# design.net
KiCad netlist of a schematic drawn in EasyEDA Pro
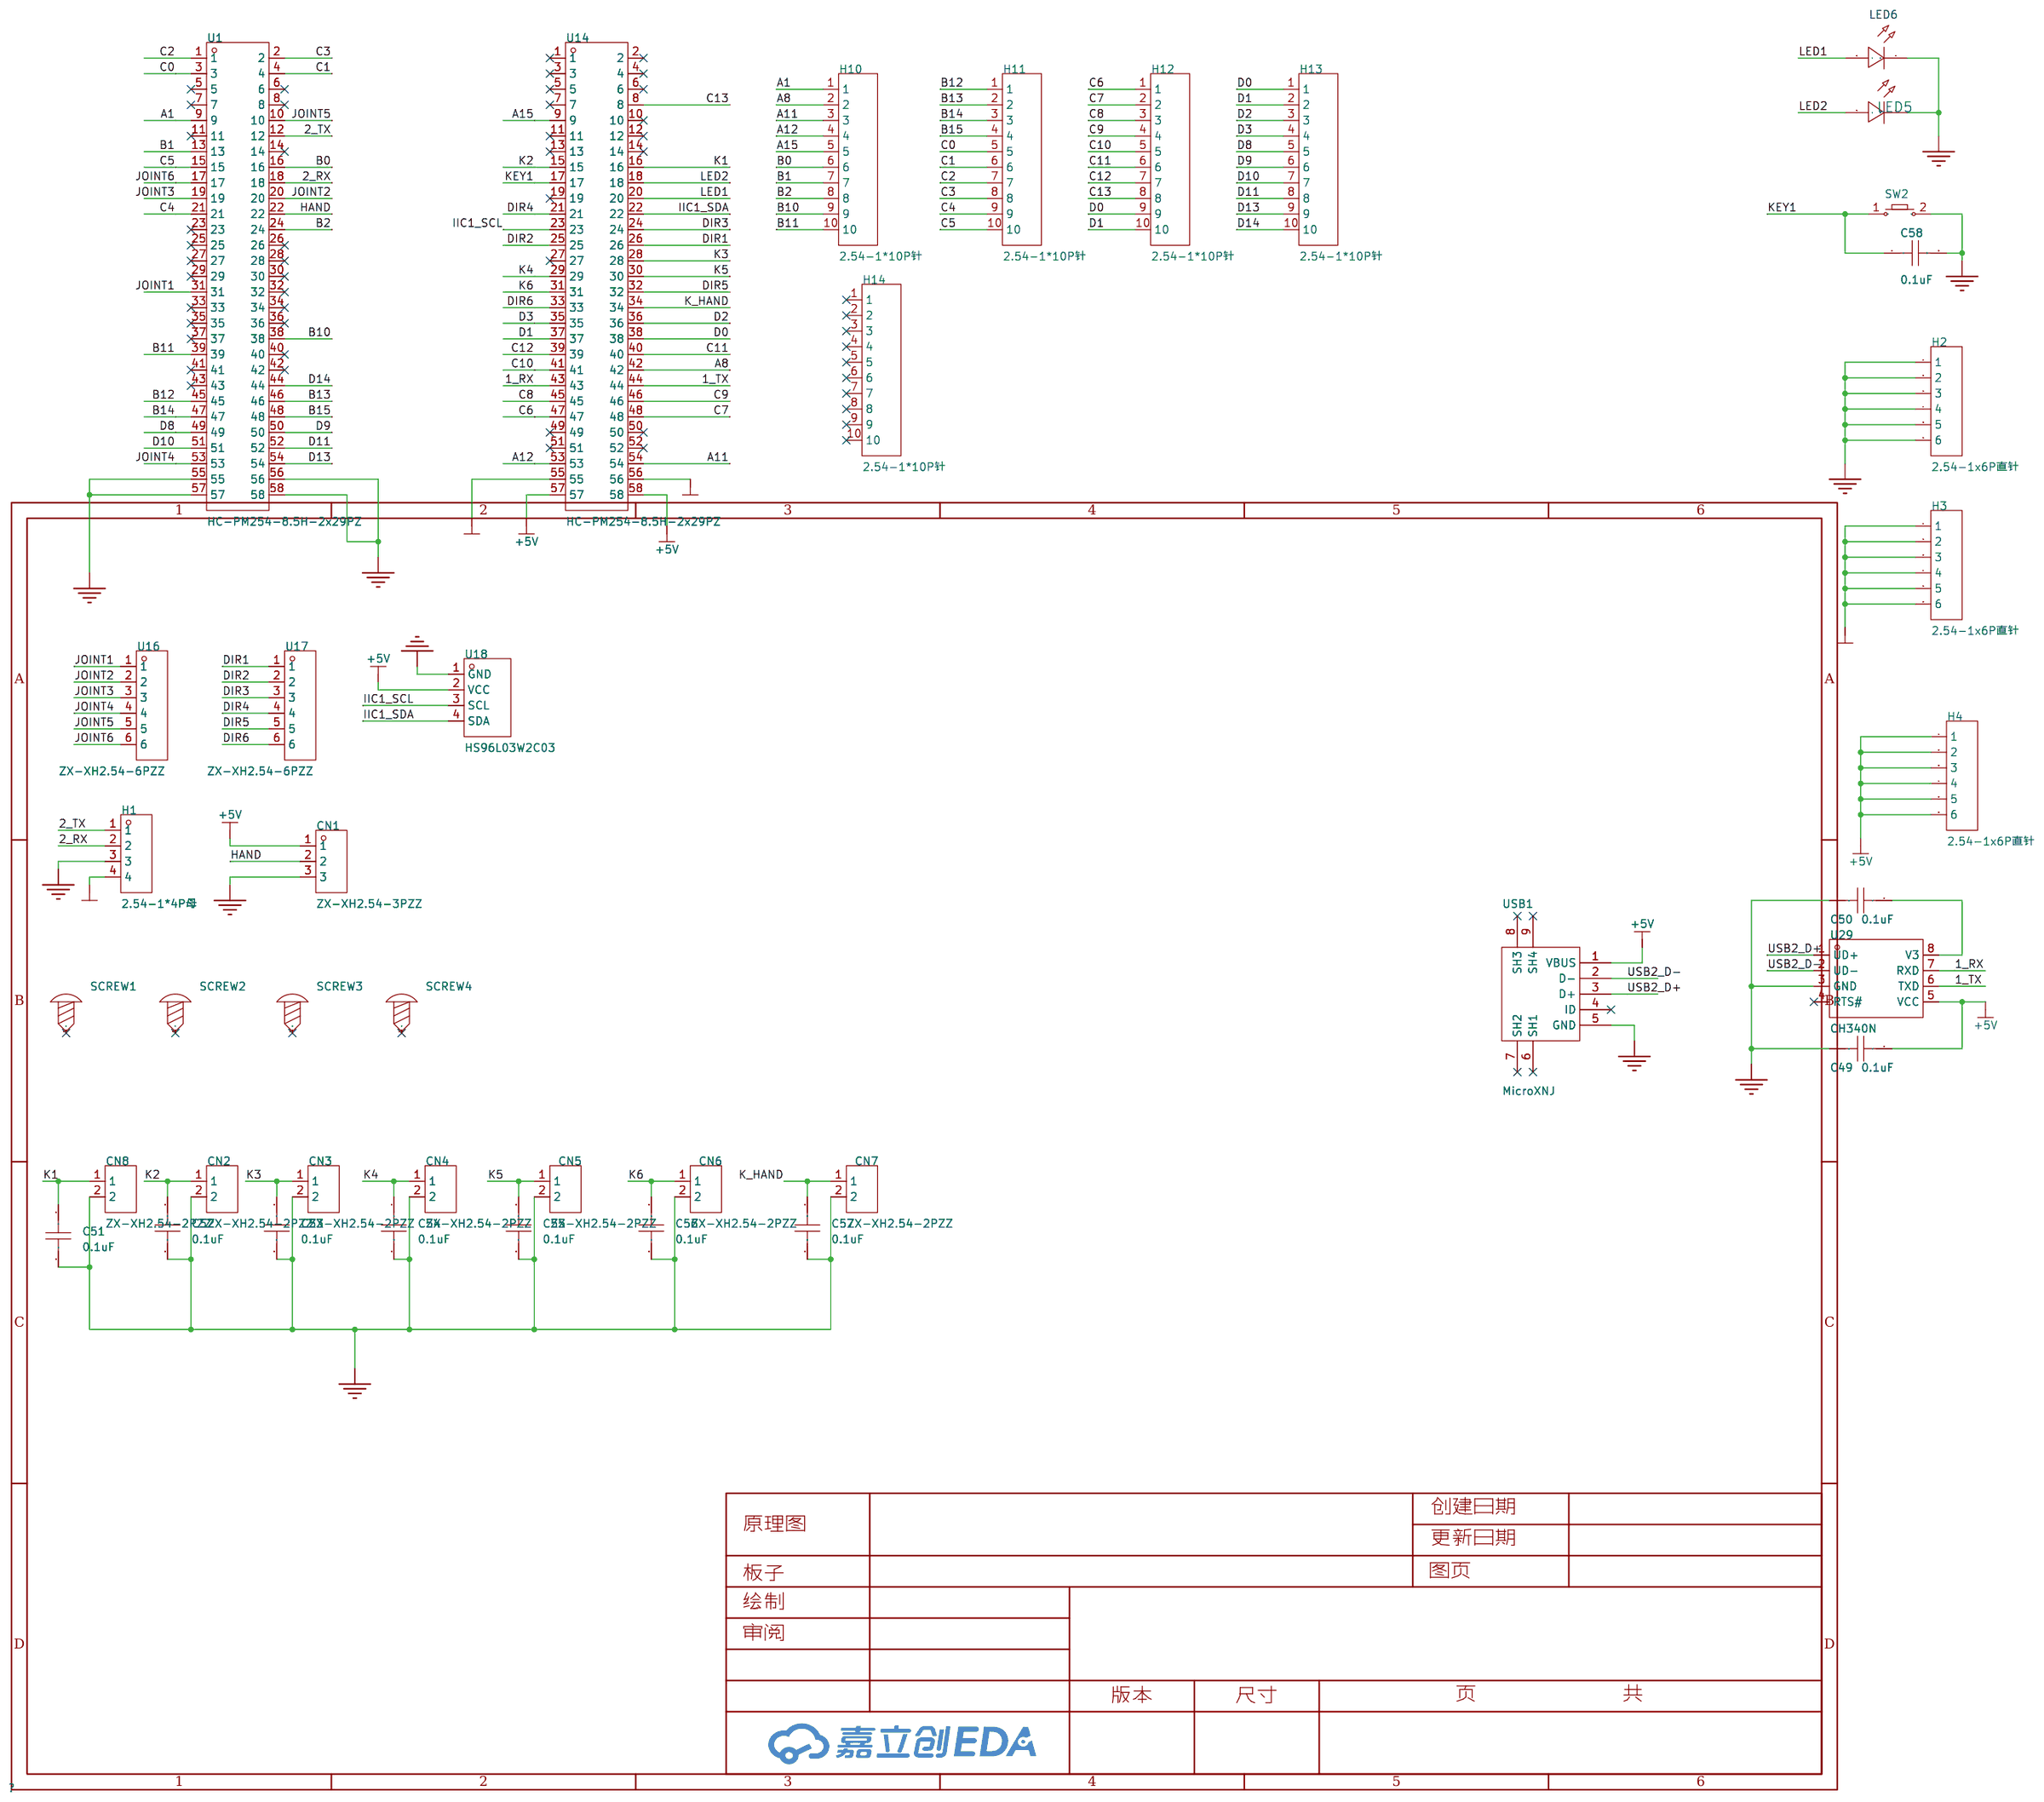
[diagram p0: 控制]
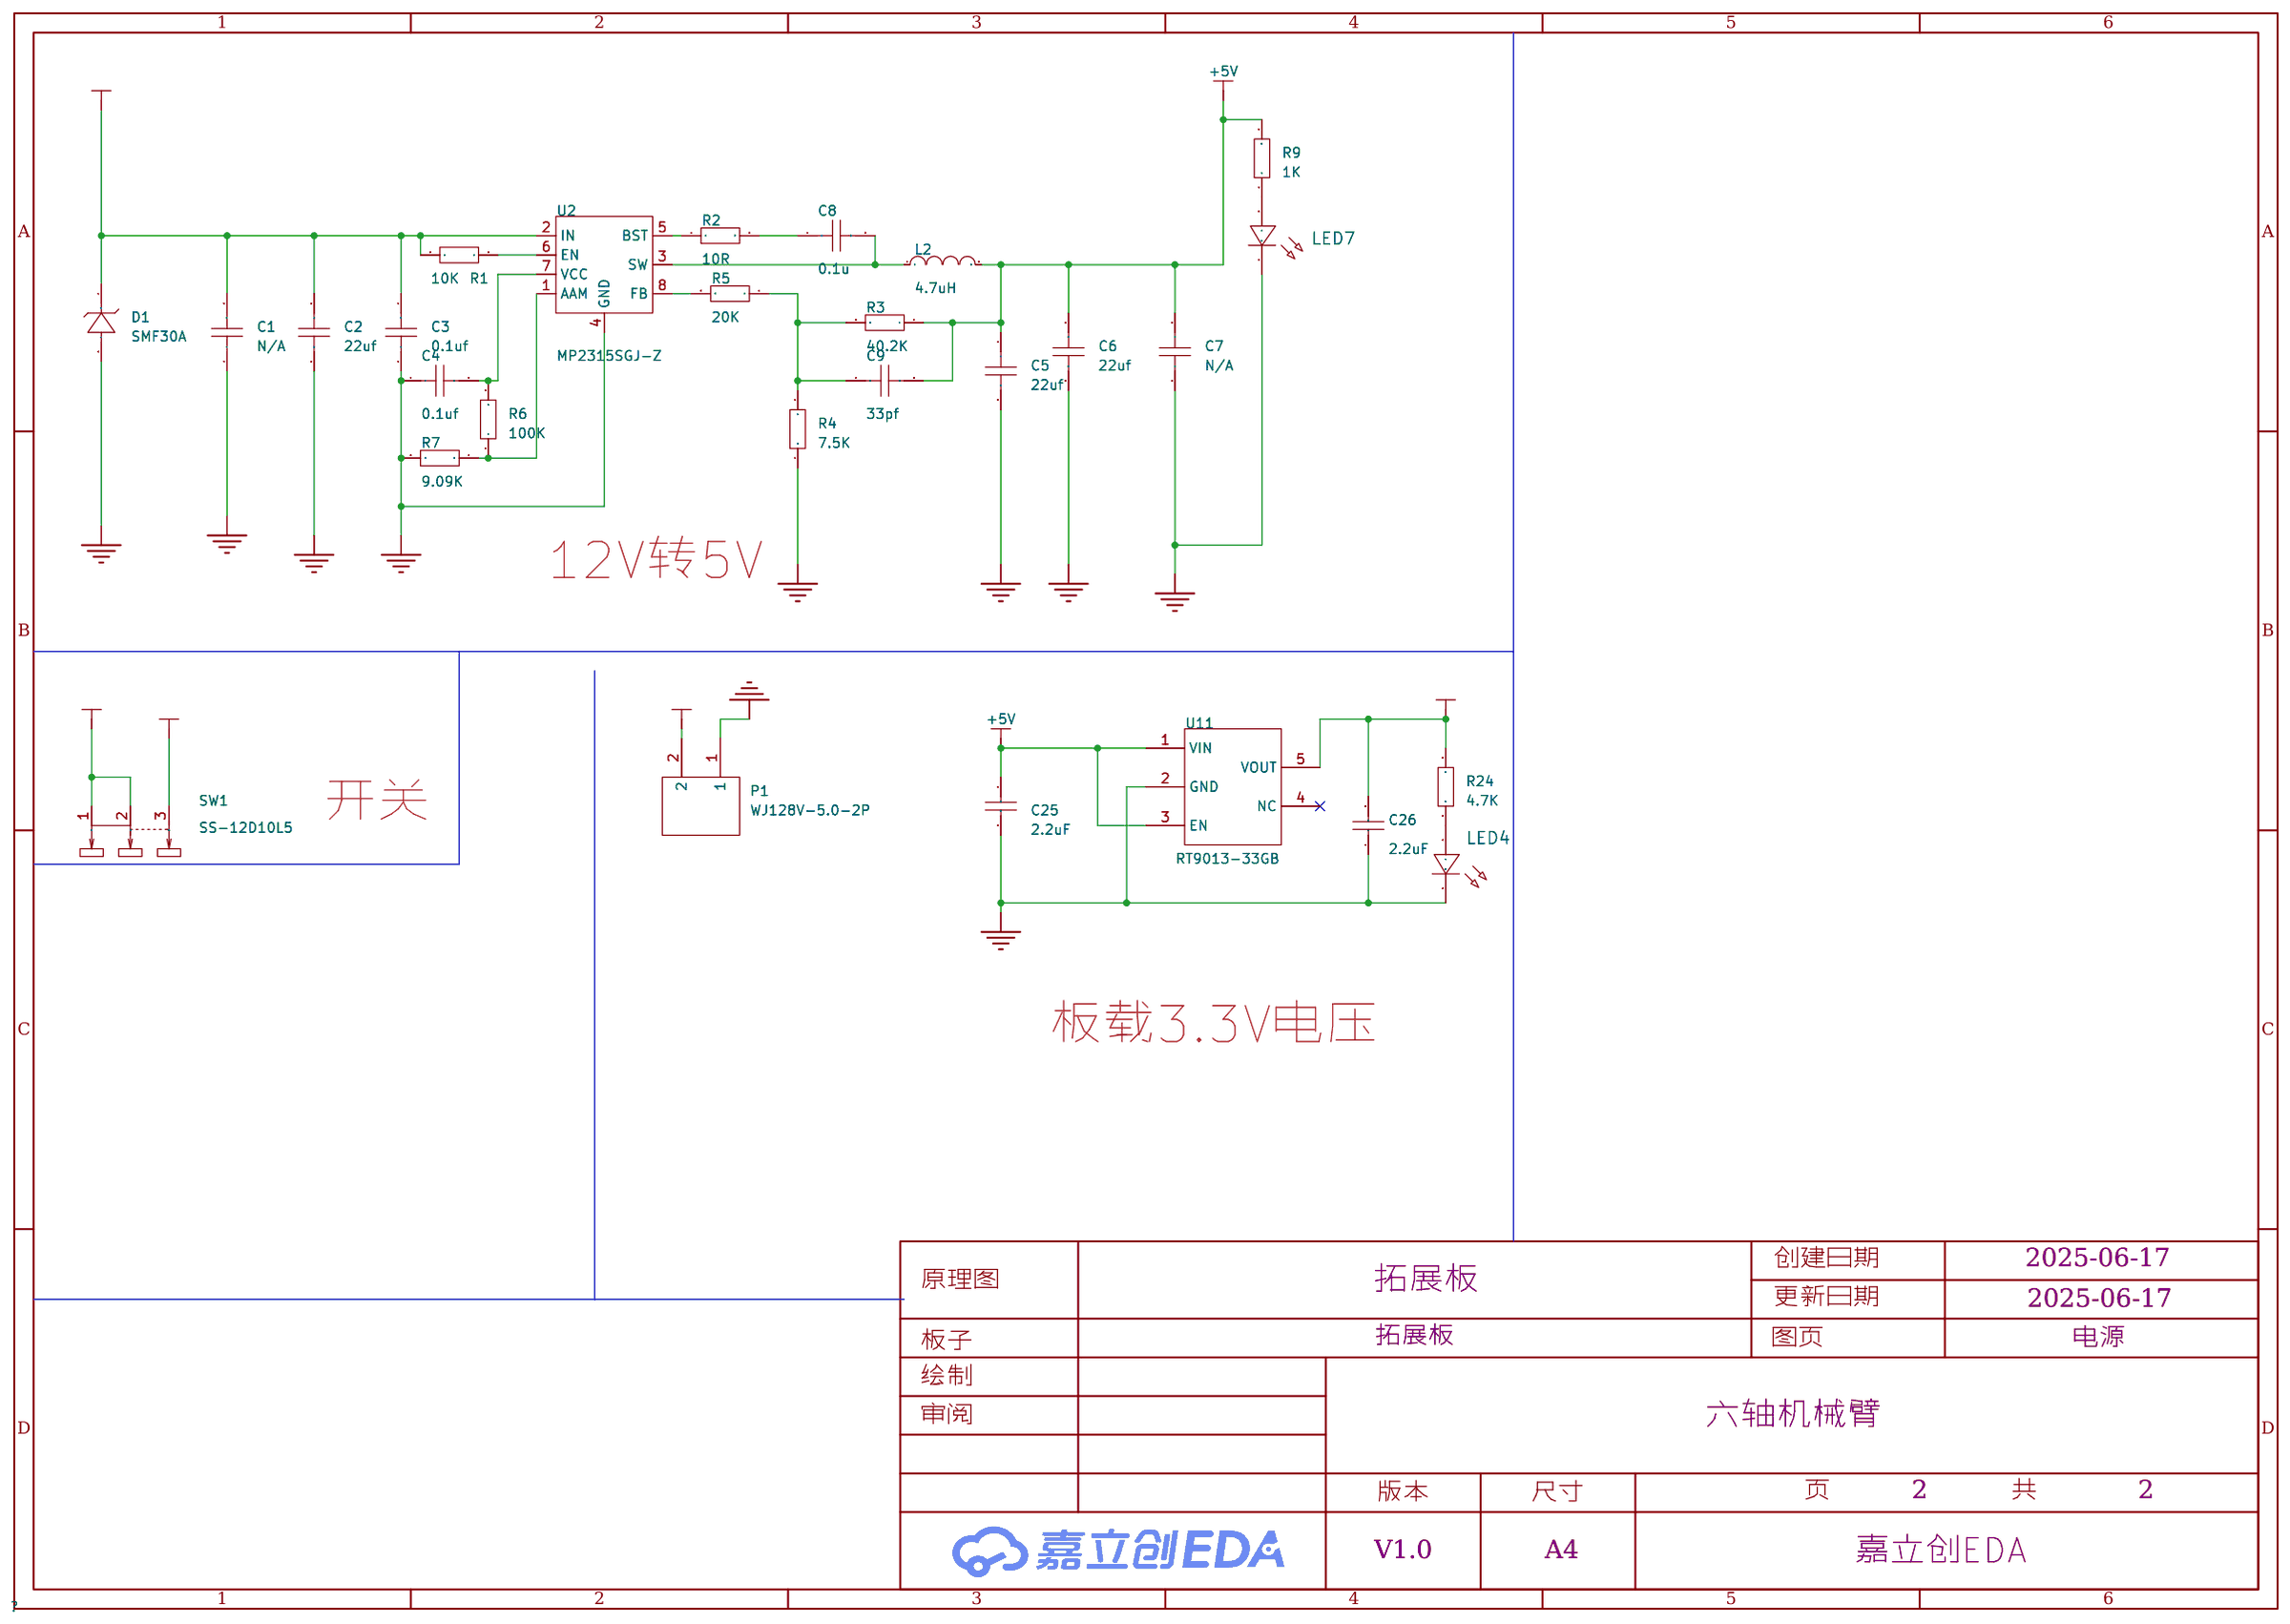
[diagram p1: 电源]

(export (version "E")
  (design (tool "Eeschema 10.0.6"))
  (components
    (comp (ref "C49")
      (value "0.1uF")
      (footprint "easyedapro:C0805")
      (libsource (lib "easyedapro") (part "CapAcitance"))
    )
    (comp (ref "C50")
      (value "0.1uF")
      (footprint "easyedapro:C0805")
      (libsource (lib "easyedapro") (part "CapAcitance"))
    )
    (comp (ref "C51")
      (value "0.1uF")
      (footprint "easyedapro:C0805")
      (libsource (lib "easyedapro") (part "CapAcitance"))
    )
    (comp (ref "C52")
      (value "0.1uF")
      (footprint "easyedapro:C0805")
      (libsource (lib "easyedapro") (part "CapAcitance"))
    )
    (comp (ref "C53")
      (value "0.1uF")
      (footprint "easyedapro:C0805")
      (libsource (lib "easyedapro") (part "CapAcitance"))
    )
    (comp (ref "C54")
      (value "0.1uF")
      (footprint "easyedapro:C0805")
      (libsource (lib "easyedapro") (part "CapAcitance"))
    )
    (comp (ref "C55")
      (value "0.1uF")
      (footprint "easyedapro:C0805")
      (libsource (lib "easyedapro") (part "CapAcitance"))
    )
    (comp (ref "C56")
      (value "0.1uF")
      (footprint "easyedapro:C0805")
      (libsource (lib "easyedapro") (part "CapAcitance"))
    )
    (comp (ref "C57")
      (value "0.1uF")
      (footprint "easyedapro:C0805")
      (libsource (lib "easyedapro") (part "CapAcitance"))
    )
    (comp (ref "C58")
      (value "0.1uF")
      (footprint "easyedapro:C0805")
      (libsource (lib "easyedapro") (part "CapAcitance"))
    )
    (comp (ref "CN1")
      (value "ZX-XH2.54-3PZZ")
      (footprint "easyedapro:CONN-TH_3P-P2.54_2501S-3P")
      (fields (field (name "Manufacturer") "Megastar(兆星)"))
      (libsource (lib "easyedapro") (part "ZX-XH2.54-3PZZ"))
    )
    (comp (ref "CN2")
      (value "ZX-XH2.54-2PZZ")
      (footprint "easyedapro:CONN-TH_2P-P2.50_HX25003-2A")
      (fields (field (name "Manufacturer") "Megastar(兆星)"))
      (libsource (lib "easyedapro") (part "ZX-XH2.54-2PZZ"))
    )
    (comp (ref "CN3")
      (value "ZX-XH2.54-2PZZ")
      (footprint "easyedapro:CONN-TH_2P-P2.50_HX25003-2A")
      (fields (field (name "Manufacturer") "Megastar(兆星)"))
      (libsource (lib "easyedapro") (part "ZX-XH2.54-2PZZ"))
    )
    (comp (ref "CN4")
      (value "ZX-XH2.54-2PZZ")
      (footprint "easyedapro:CONN-TH_2P-P2.50_HX25003-2A")
      (fields (field (name "Manufacturer") "Megastar(兆星)"))
      (libsource (lib "easyedapro") (part "ZX-XH2.54-2PZZ"))
    )
    (comp (ref "CN5")
      (value "ZX-XH2.54-2PZZ")
      (footprint "easyedapro:CONN-TH_2P-P2.50_HX25003-2A")
      (fields (field (name "Manufacturer") "Megastar(兆星)"))
      (libsource (lib "easyedapro") (part "ZX-XH2.54-2PZZ"))
    )
    (comp (ref "CN6")
      (value "ZX-XH2.54-2PZZ")
      (footprint "easyedapro:CONN-TH_2P-P2.50_HX25003-2A")
      (fields (field (name "Manufacturer") "Megastar(兆星)"))
      (libsource (lib "easyedapro") (part "ZX-XH2.54-2PZZ"))
    )
    (comp (ref "CN7")
      (value "ZX-XH2.54-2PZZ")
      (footprint "easyedapro:CONN-TH_2P-P2.50_HX25003-2A")
      (fields (field (name "Manufacturer") "Megastar(兆星)"))
      (libsource (lib "easyedapro") (part "ZX-XH2.54-2PZZ"))
    )
    (comp (ref "CN8")
      (value "ZX-XH2.54-2PZZ")
      (footprint "easyedapro:CONN-TH_2P-P2.50_HX25003-2A")
      (fields (field (name "Manufacturer") "Megastar(兆星)"))
      (libsource (lib "easyedapro") (part "ZX-XH2.54-2PZZ"))
    )
    (comp (ref "H1")
      (value "2.54-1*4P母")
      (footprint "easyedapro:HDR-TH_4P-P2.54-V-F")
      (fields (field (name "Manufacturer") "BOOMELE(博穆精密)"))
      (libsource (lib "easyedapro") (part "2.54-1*4P母"))
    )
    (comp (ref "H2")
      (value "2.54-1x6P直针")
      (footprint "easyedapro:HDR-TH_6P-P2.54-V-M-1")
      (fields (field (name "Manufacturer") "BOOMELE(博穆精密)"))
      (libsource (lib "easyedapro") (part "Header-Male-2.54_1x6"))
    )
    (comp (ref "H3")
      (value "2.54-1x6P直针")
      (footprint "easyedapro:HDR-TH_6P-P2.54-V-M-1")
      (fields (field (name "Manufacturer") "BOOMELE(博穆精密)"))
      (libsource (lib "easyedapro") (part "Header-Male-2.54_1x6"))
    )
    (comp (ref "H4")
      (value "2.54-1x6P直针")
      (footprint "easyedapro:HDR-TH_6P-P2.54-V-M-1")
      (fields (field (name "Manufacturer") "BOOMELE(博穆精密)"))
      (libsource (lib "easyedapro") (part "Header-Male-2.54_1x6"))
    )
    (comp (ref "H10")
      (value "2.54-1*10P针")
      (footprint "easyedapro:HDR-TH_10P-P2.54-V-M-1")
      (fields (field (name "Manufacturer") "BOOMELE(博穆精密)"))
      (libsource (lib "easyedapro") (part "Header-Male-2.54_1x10"))
    )
    (comp (ref "H11")
      (value "2.54-1*10P针")
      (footprint "easyedapro:HDR-TH_10P-P2.54-V-M-1")
      (fields (field (name "Manufacturer") "BOOMELE(博穆精密)"))
      (libsource (lib "easyedapro") (part "Header-Male-2.54_1x10"))
    )
    (comp (ref "H12")
      (value "2.54-1*10P针")
      (footprint "easyedapro:HDR-TH_10P-P2.54-V-M-1")
      (fields (field (name "Manufacturer") "BOOMELE(博穆精密)"))
      (libsource (lib "easyedapro") (part "Header-Male-2.54_1x10"))
    )
    (comp (ref "H13")
      (value "2.54-1*10P针")
      (footprint "easyedapro:HDR-TH_10P-P2.54-V-M-1")
      (fields (field (name "Manufacturer") "BOOMELE(博穆精密)"))
      (libsource (lib "easyedapro") (part "Header-Male-2.54_1x10"))
    )
    (comp (ref "H14")
      (value "2.54-1*10P针")
      (footprint "easyedapro:HDR-TH_10P-P2.54-V-M-1")
      (fields (field (name "Manufacturer") "BOOMELE(博穆精密)"))
      (libsource (lib "easyedapro") (part "Header-Male-2.54_1x10"))
    )
    (comp (ref "LED5")
      (value "~")
      (footprint "easyedapro:LED_0603")
      (libsource (lib "easyedapro") (part "LED_R"))
    )
    (comp (ref "LED6")
      (value "~")
      (footprint "easyedapro:LED_0603")
      (libsource (lib "easyedapro") (part "LED_G"))
    )
    (comp (ref "SCREW1")
      (value "~")
      (footprint "easyedapro:M2螺丝")
      (libsource (lib "easyedapro") (part "螺丝孔"))
    )
    (comp (ref "SCREW2")
      (value "~")
      (footprint "easyedapro:M2螺丝")
      (libsource (lib "easyedapro") (part "螺丝孔"))
    )
    (comp (ref "SCREW3")
      (value "~")
      (footprint "easyedapro:M2螺丝")
      (libsource (lib "easyedapro") (part "螺丝孔"))
    )
    (comp (ref "SCREW4")
      (value "~")
      (footprint "easyedapro:M2螺丝")
      (libsource (lib "easyedapro") (part "螺丝孔"))
    )
    (comp (ref "SW2")
      (value "~")
      (footprint "easyedapro:Key_SMD_3x4x2")
      (libsource (lib "easyedapro") (part "轻触按键x2"))
    )
    (comp (ref "U1")
      (value "HC-PM254-8.5H-2x29PZ")
      (footprint "easyedapro:HDR-TH_58P-P2.54-V-F-R2-C29-S2.54")
      (fields (field (name "Manufacturer") "HC(虹成电子)"))
      (libsource (lib "easyedapro") (part "HC-PM254-8.5H-2X29PZ"))
    )
    (comp (ref "U14")
      (value "HC-PM254-8.5H-2x29PZ")
      (footprint "easyedapro:HDR-TH_58P-P2.54-V-F-R2-C29-S2.54")
      (fields (field (name "Manufacturer") "HC(虹成电子)"))
      (libsource (lib "easyedapro") (part "HC-PM254-8.5H-2X29PZ"))
    )
    (comp (ref "U16")
      (value "ZX-XH2.54-6PZZ")
      (footprint "easyedapro:CONN-TH_6P-P2.50_ZX-XH2.54-6PZZ")
      (fields (field (name "Manufacturer") "Megastar(兆星)"))
      (libsource (lib "easyedapro") (part "ZX-XH2.54-6PZZ"))
    )
    (comp (ref "U17")
      (value "ZX-XH2.54-6PZZ")
      (footprint "easyedapro:CONN-TH_6P-P2.50_ZX-XH2.54-6PZZ")
      (fields (field (name "Manufacturer") "Megastar(兆星)"))
      (libsource (lib "easyedapro") (part "ZX-XH2.54-6PZZ"))
    )
    (comp (ref "U18")
      (value "HS96L03W2C03")
      (footprint "easyedapro:OLED-TH_L27.8-W27.2-P2.54_C9900033791")
      (description "主控芯片:SSD1315;接口类型:I2C;尺寸(inch):0.96;像素分辨率:128x64;")
      (fields (field (name "Manufacturer") "HS(汉昇)"))
      (libsource (lib "easyedapro") (part "HS96L03W2C03"))
    )
    (comp (ref "U29")
      (value "CH340N")
      (footprint "easyedapro:SOP-8_L4.9-W3.9-P1.27-LS6.0-BL")
      (description "应用功能:USB转串口;接口协议:USB 2.0;通道数:1;数据速率:2Mbps;")
      (fields (field (name "Manufacturer") "WCH(南京沁恒)"))
      (libsource (lib "easyedapro") (part "CH340N_C2977777"))
    )
    (comp (ref "USB1")
      (value "MicroXNJ")
      (footprint "easyedapro:MICRO-USB-SMD_MICROXNJ")
      (description "连接器类型:Micro-B;标准:USB 2.0;公母:母;安装方式:卧贴;触点数量:5P;端口数量:1;额定电流 - 电源:1.8A;工作温度范围:-20°C~+85°C;")
      (fields (field (name "Manufacturer") "SHOU HAN(首韩)"))
      (libsource (lib "easyedapro") (part "MICROXNJ"))
    )
    (comp (ref "C1")
      (value "N/A")
      (footprint "easyedapro:C0805")
      (libsource (lib "easyedapro") (part "CapAcitance"))
    )
    (comp (ref "C2")
      (value "22uf")
      (footprint "easyedapro:C0805")
      (libsource (lib "easyedapro") (part "CapAcitance"))
    )
    (comp (ref "C3")
      (value "0.1uf")
      (footprint "easyedapro:C0805")
      (libsource (lib "easyedapro") (part "CapAcitance"))
    )
    (comp (ref "C4")
      (value "0.1uf")
      (footprint "easyedapro:C0805")
      (libsource (lib "easyedapro") (part "CapAcitance"))
    )
    (comp (ref "C5")
      (value "22uf")
      (footprint "easyedapro:C0805")
      (libsource (lib "easyedapro") (part "CapAcitance"))
    )
    (comp (ref "C6")
      (value "22uf")
      (footprint "easyedapro:C0805")
      (libsource (lib "easyedapro") (part "CapAcitance"))
    )
    (comp (ref "C7")
      (value "N/A")
      (footprint "easyedapro:C0805")
      (libsource (lib "easyedapro") (part "CapAcitance"))
    )
    (comp (ref "C8")
      (value "0.1u")
      (footprint "easyedapro:C0805")
      (libsource (lib "easyedapro") (part "CapAcitance"))
    )
    (comp (ref "C9")
      (value "33pf")
      (footprint "easyedapro:C0805")
      (libsource (lib "easyedapro") (part "CapAcitance"))
    )
    (comp (ref "C25")
      (value "2.2uF")
      (footprint "easyedapro:C0603")
      (description "容值:100nF;精度:±10%;额定电压:50V;材质(温度系数):X7R;")
      (fields (field (name "Manufacturer Part") "0603B104K500NT") (field (name "Manufacturer") "FH(风华)"))
      (libsource (lib "easyedapro") (part "0603B104K500NT"))
    )
    (comp (ref "C26")
      (value "2.2uF")
      (footprint "easyedapro:C0603")
      (description "容值:100nF;精度:±10%;额定电压:50V;材质(温度系数):X7R;")
      (fields (field (name "Manufacturer Part") "0603B104K500NT") (field (name "Manufacturer") "FH(风华)"))
      (libsource (lib "easyedapro") (part "0603B104K500NT"))
    )
    (comp (ref "D1")
      (value "SMF30A")
      (fields (field (name "Manufacturer") "晶导微电子"))
      (libsource (lib "easyedapro") (part "SMF5.0A_C19077497"))
    )
    (comp (ref "L2")
      (value "4.7uH")
      (footprint "easyedapro:IND-SMD_L4.4-W4.2")
      (description "电感值:4.7uH;精度:±20%;额定电流:2.8A;饱和电流(Isat):3A;类型:一体成型电感;")
      (fields (field (name "Manufacturer Part") "FXL0530-4R7-M") (field (name "Manufacturer") "cjiang(长江微电)"))
      (libsource (lib "easyedapro") (part "FXL0420-4R7-M"))
    )
    (comp (ref "LED4")
      (value "~")
      (footprint "easyedapro:LED_0603")
      (libsource (lib "easyedapro") (part "LED_R"))
    )
    (comp (ref "LED7")
      (value "~")
      (footprint "easyedapro:LED_0603")
      (libsource (lib "easyedapro") (part "LED_R"))
    )
    (comp (ref "P1")
      (value "WJ128V-5.0-2P")
      (footprint "easyedapro:CONN-TH_2P-P5.00_WJ128V-5.0-2P")
      (fields (field (name "Manufacturer") "KANGNEX(康奈克斯电气)"))
      (libsource (lib "easyedapro") (part "WJ128V-5.0-2P"))
    )
    (comp (ref "R1") (value "10K") (footprint "easyedapro:R0603") (libsource (lib "easyedapro") (part "电阻")))
    (comp (ref "R2") (value "10R") (footprint "easyedapro:R0603") (libsource (lib "easyedapro") (part "电阻")))
    (comp (ref "R3")
      (value "40.2K")
      (footprint "easyedapro:R0603")
      (libsource (lib "easyedapro") (part "电阻"))
    )
    (comp (ref "R4") (value "7.5K") (footprint "easyedapro:R0603") (libsource (lib "easyedapro") (part "电阻")))
    (comp (ref "R5") (value "20K") (footprint "easyedapro:R0603") (libsource (lib "easyedapro") (part "电阻")))
    (comp (ref "R6") (value "100K") (footprint "easyedapro:R0603") (libsource (lib "easyedapro") (part "电阻")))
    (comp (ref "R7")
      (value "9.09K")
      (footprint "easyedapro:R0603")
      (libsource (lib "easyedapro") (part "电阻"))
    )
    (comp (ref "R9") (value "1K") (footprint "easyedapro:R0603") (libsource (lib "easyedapro") (part "电阻")))
    (comp (ref "R24") (value "4.7K") (libsource (lib "easyedapro") (part "电阻")))
    (comp (ref "SW1")
      (value "SS-12D10L5")
      (footprint "easyedapro:SW-TH_SS-12D10L5")
      (description "电路结构:单刀双掷;安装方式:直插;开关颜色:黑色;额定电流(DC):3A;额定电压(DC):125V;额定电流(AC):3A;额定电压(AC):125V;机械寿命:1万次;")
      (fields (field (name "Manufacturer") "XKB Connectivity(中国星坤)"))
      (libsource (lib "easyedapro") (part "SS-12D10L5"))
    )
    (comp (ref "U2")
      (value "MP2315SGJ-Z")
      (footprint "easyedapro:TSOT-23-8_L2.9-W1.6-P0.65-LS2.8-BL")
      (description "功能类型:降压型;输出类型:固定;工作电压:4.5V~24V;输出电压:800mV~22.8V;输出电流:3A;")
      (fields (field (name "Manufacturer") "MPS(芯源)"))
      (libsource (lib "easyedapro") (part "MP2315SGJ-Z"))
    )
    (comp (ref "U11")
      (value "RT9013-33GB")
      (footprint "easyedapro:SOT-23-5_L3.0-W1.7-P0.95-LS2.8-BL")
      (description "输出类型:固定;最大输入电压:5.5V;输出电压:3.3V;输出电流:500mA;电源纹波抑制比(PSRR):50dB@(10kHz);输出极性:正极;")
      (fields (field (name "Manufacturer") "RICHTEK(立锜)"))
      (libsource (lib "easyedapro") (part "RT9013-33GB"))
    )
  )
  (nets
    (net (code "1") (name "+5V") (class "Default")
      (node (ref "C25") (pin "2") (pinfunction "2_2") (pintype "input"))
      (node (ref "C49") (pin "1") (pinfunction "1_1") (pintype "input"))
      (node (ref "C5") (pin "1") (pinfunction "1_1") (pintype "input"))
      (node (ref "C6") (pin "1") (pinfunction "1_1") (pintype "input"))
      (node (ref "C7") (pin "1") (pinfunction "1_1") (pintype "input"))
      (node (ref "C9") (pin "2") (pinfunction "2_2") (pintype "input"))
      (node (ref "CN1") (pin "1") (pinfunction "1_1") (pintype "unspecified"))
      (node (ref "H4") (pin "1") (pinfunction "1_1") (pintype "input"))
      (node (ref "H4") (pin "2") (pinfunction "2_2") (pintype "input"))
      (node (ref "H4") (pin "3") (pinfunction "3_3") (pintype "input"))
      (node (ref "H4") (pin "4") (pinfunction "4_4") (pintype "input"))
      (node (ref "H4") (pin "5") (pinfunction "5_5") (pintype "input"))
      (node (ref "H4") (pin "6") (pinfunction "6_6") (pintype "input"))
      (node (ref "L2") (pin "2") (pinfunction "2_2") (pintype "unspecified"))
      (node (ref "R3") (pin "1") (pinfunction "1_1") (pintype "input"))
      (node (ref "R9") (pin "2") (pinfunction "2_2") (pintype "input"))
      (node (ref "U11") (pin "1") (pinfunction "VIN_1") (pintype "unspecified"))
      (node (ref "U11") (pin "3") (pinfunction "EN_3") (pintype "unspecified"))
      (node (ref "U14") (pin "57") (pinfunction "57_57") (pintype "unspecified"))
      (node (ref "U14") (pin "58") (pinfunction "58_58") (pintype "unspecified"))
      (node (ref "U18") (pin "2") (pinfunction "VCC_2") (pintype "unspecified"))
      (node (ref "U29") (pin "5") (pinfunction "VCC_5") (pintype "unspecified"))
      (node (ref "USB1") (pin "1") (pinfunction "VBUS_1") (pintype "unspecified"))
    )
    (net (code "2") (name "1_RX") (class "Default")
      (node (ref "U14") (pin "43") (pinfunction "43_43") (pintype "unspecified"))
      (node (ref "U29") (pin "7") (pinfunction "RXD_7") (pintype "unspecified"))
    )
    (net (code "3") (name "1_TX") (class "Default")
      (node (ref "U14") (pin "44") (pinfunction "44_44") (pintype "unspecified"))
      (node (ref "U29") (pin "6") (pinfunction "TXD_6") (pintype "unspecified"))
    )
    (net (code "4") (name "2_RX") (class "Default")
      (node (ref "H1") (pin "2") (pinfunction "2_2") (pintype "unspecified"))
      (node (ref "U1") (pin "18") (pinfunction "18_18") (pintype "unspecified"))
    )
    (net (code "5") (name "2_TX") (class "Default")
      (node (ref "H1") (pin "1") (pinfunction "1_1") (pintype "unspecified"))
      (node (ref "U1") (pin "12") (pinfunction "12_12") (pintype "unspecified"))
    )
    (net (code "6") (name "3.3V") (class "Default")
      (node (ref "C26") (pin "2") (pinfunction "2_2") (pintype "input"))
      (node (ref "H1") (pin "4") (pinfunction "4_4") (pintype "unspecified"))
      (node (ref "H3") (pin "1") (pinfunction "1_1") (pintype "input"))
      (node (ref "H3") (pin "2") (pinfunction "2_2") (pintype "input"))
      (node (ref "H3") (pin "3") (pinfunction "3_3") (pintype "input"))
      (node (ref "H3") (pin "4") (pinfunction "4_4") (pintype "input"))
      (node (ref "H3") (pin "5") (pinfunction "5_5") (pintype "input"))
      (node (ref "H3") (pin "6") (pinfunction "6_6") (pintype "input"))
      (node (ref "R24") (pin "2") (pinfunction "2_2") (pintype "input"))
      (node (ref "U11") (pin "5") (pinfunction "VOUT_5") (pintype "unspecified"))
      (node (ref "U14") (pin "55") (pinfunction "55_55") (pintype "unspecified"))
      (node (ref "U14") (pin "56") (pinfunction "56_56") (pintype "unspecified"))
    )
    (net (code "7") (name "12V_IN") (class "Default")
      (node (ref "P1") (pin "2") (pinfunction "2_2") (pintype "unspecified"))
      (node (ref "SW1") (pin "3") (pinfunction "3_3") (pintype "unspecified"))
    )
    (net (code "8") (name "12V_OUT") (class "Default")
      (node (ref "C1") (pin "2") (pinfunction "2_2") (pintype "input"))
      (node (ref "C2") (pin "1") (pinfunction "1_1") (pintype "input"))
      (node (ref "C3") (pin "1") (pinfunction "1_1") (pintype "input"))
      (node (ref "D1") (pin "1") (pinfunction "K_1") (pintype "unspecified"))
      (node (ref "R1") (pin "1") (pinfunction "1_1") (pintype "input"))
      (node (ref "SW1") (pin "1") (pinfunction "1_1") (pintype "unspecified"))
      (node (ref "SW1") (pin "2") (pinfunction "2_2") (pintype "unspecified"))
      (node (ref "U2") (pin "2") (pinfunction "IN_2") (pintype "unspecified"))
    )
    (net (code "9") (name "A1") (class "Default")
      (node (ref "H10") (pin "1") (pinfunction "1_1") (pintype "unspecified"))
      (node (ref "U1") (pin "9") (pinfunction "9_9") (pintype "unspecified"))
    )
    (net (code "10") (name "A8") (class "Default")
      (node (ref "H10") (pin "2") (pinfunction "2_2") (pintype "unspecified"))
      (node (ref "U14") (pin "42") (pinfunction "42_42") (pintype "unspecified"))
    )
    (net (code "11") (name "A11") (class "Default")
      (node (ref "H10") (pin "3") (pinfunction "3_3") (pintype "unspecified"))
      (node (ref "U14") (pin "54") (pinfunction "54_54") (pintype "unspecified"))
    )
    (net (code "12") (name "A12") (class "Default")
      (node (ref "H10") (pin "4") (pinfunction "4_4") (pintype "unspecified"))
      (node (ref "U14") (pin "53") (pinfunction "53_53") (pintype "unspecified"))
    )
    (net (code "13") (name "A15") (class "Default")
      (node (ref "H10") (pin "5") (pinfunction "5_5") (pintype "unspecified"))
      (node (ref "U14") (pin "9") (pinfunction "9_9") (pintype "unspecified"))
    )
    (net (code "14") (name "B0") (class "Default")
      (node (ref "H10") (pin "6") (pinfunction "6_6") (pintype "unspecified"))
      (node (ref "U1") (pin "16") (pinfunction "16_16") (pintype "unspecified"))
    )
    (net (code "15") (name "B1") (class "Default")
      (node (ref "H10") (pin "7") (pinfunction "7_7") (pintype "unspecified"))
      (node (ref "U1") (pin "13") (pinfunction "13_13") (pintype "unspecified"))
    )
    (net (code "16") (name "B2") (class "Default")
      (node (ref "H10") (pin "8") (pinfunction "8_8") (pintype "unspecified"))
      (node (ref "U1") (pin "24") (pinfunction "24_24") (pintype "unspecified"))
    )
    (net (code "17") (name "B10") (class "Default")
      (node (ref "H10") (pin "9") (pinfunction "9_9") (pintype "unspecified"))
      (node (ref "U1") (pin "38") (pinfunction "38_38") (pintype "unspecified"))
    )
    (net (code "18") (name "B11") (class "Default")
      (node (ref "H10") (pin "10") (pinfunction "10_10") (pintype "unspecified"))
      (node (ref "U1") (pin "39") (pinfunction "39_39") (pintype "unspecified"))
    )
    (net (code "19") (name "B12") (class "Default")
      (node (ref "H11") (pin "1") (pinfunction "1_1") (pintype "unspecified"))
      (node (ref "U1") (pin "45") (pinfunction "45_45") (pintype "unspecified"))
    )
    (net (code "20") (name "B13") (class "Default")
      (node (ref "H11") (pin "2") (pinfunction "2_2") (pintype "unspecified"))
      (node (ref "U1") (pin "46") (pinfunction "46_46") (pintype "unspecified"))
    )
    (net (code "21") (name "B14") (class "Default")
      (node (ref "H11") (pin "3") (pinfunction "3_3") (pintype "unspecified"))
      (node (ref "U1") (pin "47") (pinfunction "47_47") (pintype "unspecified"))
    )
    (net (code "22") (name "B15") (class "Default")
      (node (ref "H11") (pin "4") (pinfunction "4_4") (pintype "unspecified"))
      (node (ref "U1") (pin "48") (pinfunction "48_48") (pintype "unspecified"))
    )
    (net (code "23") (name "C0") (class "Default")
      (node (ref "H11") (pin "5") (pinfunction "5_5") (pintype "unspecified"))
      (node (ref "U1") (pin "3") (pinfunction "3_3") (pintype "unspecified"))
    )
    (net (code "24") (name "C1") (class "Default")
      (node (ref "H11") (pin "6") (pinfunction "6_6") (pintype "unspecified"))
      (node (ref "U1") (pin "4") (pinfunction "4_4") (pintype "unspecified"))
    )
    (net (code "25") (name "C2") (class "Default")
      (node (ref "H11") (pin "7") (pinfunction "7_7") (pintype "unspecified"))
      (node (ref "U1") (pin "1") (pinfunction "1_1") (pintype "unspecified"))
    )
    (net (code "26") (name "C3") (class "Default")
      (node (ref "H11") (pin "8") (pinfunction "8_8") (pintype "unspecified"))
      (node (ref "U1") (pin "2") (pinfunction "2_2") (pintype "unspecified"))
    )
    (net (code "27") (name "C4") (class "Default")
      (node (ref "H11") (pin "9") (pinfunction "9_9") (pintype "unspecified"))
      (node (ref "U1") (pin "21") (pinfunction "21_21") (pintype "unspecified"))
    )
    (net (code "28") (name "C5") (class "Default")
      (node (ref "H11") (pin "10") (pinfunction "10_10") (pintype "unspecified"))
      (node (ref "U1") (pin "15") (pinfunction "15_15") (pintype "unspecified"))
    )
    (net (code "29") (name "C6") (class "Default")
      (node (ref "H12") (pin "1") (pinfunction "1_1") (pintype "unspecified"))
      (node (ref "U14") (pin "47") (pinfunction "47_47") (pintype "unspecified"))
    )
    (net (code "30") (name "C7") (class "Default")
      (node (ref "H12") (pin "2") (pinfunction "2_2") (pintype "unspecified"))
      (node (ref "U14") (pin "48") (pinfunction "48_48") (pintype "unspecified"))
    )
    (net (code "31") (name "C8") (class "Default")
      (node (ref "H12") (pin "3") (pinfunction "3_3") (pintype "unspecified"))
      (node (ref "U14") (pin "45") (pinfunction "45_45") (pintype "unspecified"))
    )
    (net (code "32") (name "C9") (class "Default")
      (node (ref "H12") (pin "4") (pinfunction "4_4") (pintype "unspecified"))
      (node (ref "U14") (pin "46") (pinfunction "46_46") (pintype "unspecified"))
    )
    (net (code "33") (name "C10") (class "Default")
      (node (ref "H12") (pin "5") (pinfunction "5_5") (pintype "unspecified"))
      (node (ref "U14") (pin "41") (pinfunction "41_41") (pintype "unspecified"))
    )
    (net (code "34") (name "C11") (class "Default")
      (node (ref "H12") (pin "6") (pinfunction "6_6") (pintype "unspecified"))
      (node (ref "U14") (pin "40") (pinfunction "40_40") (pintype "unspecified"))
    )
    (net (code "35") (name "C12") (class "Default")
      (node (ref "H12") (pin "7") (pinfunction "7_7") (pintype "unspecified"))
      (node (ref "U14") (pin "39") (pinfunction "39_39") (pintype "unspecified"))
    )
    (net (code "36") (name "C13") (class "Default")
      (node (ref "H12") (pin "8") (pinfunction "8_8") (pintype "unspecified"))
      (node (ref "U14") (pin "8") (pinfunction "8_8") (pintype "unspecified"))
    )
    (net (code "37") (name "D0") (class "Default")
      (node (ref "H12") (pin "9") (pinfunction "9_9") (pintype "unspecified"))
      (node (ref "H13") (pin "1") (pinfunction "1_1") (pintype "unspecified"))
      (node (ref "U14") (pin "38") (pinfunction "38_38") (pintype "unspecified"))
    )
    (net (code "38") (name "D1") (class "Default")
      (node (ref "H12") (pin "10") (pinfunction "10_10") (pintype "unspecified"))
      (node (ref "H13") (pin "2") (pinfunction "2_2") (pintype "unspecified"))
      (node (ref "U14") (pin "37") (pinfunction "37_37") (pintype "unspecified"))
    )
    (net (code "39") (name "D2") (class "Default")
      (node (ref "H13") (pin "3") (pinfunction "3_3") (pintype "unspecified"))
      (node (ref "U14") (pin "36") (pinfunction "36_36") (pintype "unspecified"))
    )
    (net (code "40") (name "D3") (class "Default")
      (node (ref "H13") (pin "4") (pinfunction "4_4") (pintype "unspecified"))
      (node (ref "U14") (pin "35") (pinfunction "35_35") (pintype "unspecified"))
    )
    (net (code "41") (name "D8") (class "Default")
      (node (ref "H13") (pin "5") (pinfunction "5_5") (pintype "unspecified"))
      (node (ref "U1") (pin "49") (pinfunction "49_49") (pintype "unspecified"))
    )
    (net (code "42") (name "D9") (class "Default")
      (node (ref "H13") (pin "6") (pinfunction "6_6") (pintype "unspecified"))
      (node (ref "U1") (pin "50") (pinfunction "50_50") (pintype "unspecified"))
    )
    (net (code "43") (name "D10") (class "Default")
      (node (ref "H13") (pin "7") (pinfunction "7_7") (pintype "unspecified"))
      (node (ref "U1") (pin "51") (pinfunction "51_51") (pintype "unspecified"))
    )
    (net (code "44") (name "D11") (class "Default")
      (node (ref "H13") (pin "8") (pinfunction "8_8") (pintype "unspecified"))
      (node (ref "U1") (pin "52") (pinfunction "52_52") (pintype "unspecified"))
    )
    (net (code "45") (name "D13") (class "Default")
      (node (ref "H13") (pin "9") (pinfunction "9_9") (pintype "unspecified"))
      (node (ref "U1") (pin "54") (pinfunction "54_54") (pintype "unspecified"))
    )
    (net (code "46") (name "D14") (class "Default")
      (node (ref "H13") (pin "10") (pinfunction "10_10") (pintype "unspecified"))
      (node (ref "U1") (pin "44") (pinfunction "44_44") (pintype "unspecified"))
    )
    (net (code "47") (name "DIR1") (class "Default")
      (node (ref "U14") (pin "26") (pinfunction "26_26") (pintype "unspecified"))
      (node (ref "U17") (pin "1") (pinfunction "1_1") (pintype "unspecified"))
    )
    (net (code "48") (name "DIR2") (class "Default")
      (node (ref "U14") (pin "25") (pinfunction "25_25") (pintype "unspecified"))
      (node (ref "U17") (pin "2") (pinfunction "2_2") (pintype "unspecified"))
    )
    (net (code "49") (name "DIR3") (class "Default")
      (node (ref "U14") (pin "24") (pinfunction "24_24") (pintype "unspecified"))
      (node (ref "U17") (pin "3") (pinfunction "3_3") (pintype "unspecified"))
    )
    (net (code "50") (name "DIR4") (class "Default")
      (node (ref "U14") (pin "21") (pinfunction "21_21") (pintype "unspecified"))
      (node (ref "U17") (pin "4") (pinfunction "4_4") (pintype "unspecified"))
    )
    (net (code "51") (name "DIR5") (class "Default")
      (node (ref "U14") (pin "32") (pinfunction "32_32") (pintype "unspecified"))
      (node (ref "U17") (pin "5") (pinfunction "5_5") (pintype "unspecified"))
    )
    (net (code "52") (name "DIR6") (class "Default")
      (node (ref "U14") (pin "33") (pinfunction "33_33") (pintype "unspecified"))
      (node (ref "U17") (pin "6") (pinfunction "6_6") (pintype "unspecified"))
    )
    (net (code "53") (name "GND") (class "Default")
      (node (ref "C1") (pin "1") (pinfunction "1_1") (pintype "input"))
      (node (ref "C2") (pin "2") (pinfunction "2_2") (pintype "input"))
      (node (ref "C25") (pin "1") (pinfunction "1_1") (pintype "input"))
      (node (ref "C26") (pin "1") (pinfunction "1_1") (pintype "input"))
      (node (ref "C3") (pin "2") (pinfunction "2_2") (pintype "input"))
      (node (ref "C4") (pin "1") (pinfunction "1_1") (pintype "input"))
      (node (ref "C49") (pin "2") (pinfunction "2_2") (pintype "input"))
      (node (ref "C5") (pin "2") (pinfunction "2_2") (pintype "input"))
      (node (ref "C50") (pin "2") (pinfunction "2_2") (pintype "input"))
      (node (ref "C51") (pin "2") (pinfunction "2_2") (pintype "input"))
      (node (ref "C52") (pin "2") (pinfunction "2_2") (pintype "input"))
      (node (ref "C53") (pin "2") (pinfunction "2_2") (pintype "input"))
      (node (ref "C54") (pin "2") (pinfunction "2_2") (pintype "input"))
      (node (ref "C55") (pin "2") (pinfunction "2_2") (pintype "input"))
      (node (ref "C56") (pin "2") (pinfunction "2_2") (pintype "input"))
      (node (ref "C57") (pin "2") (pinfunction "2_2") (pintype "input"))
      (node (ref "C58") (pin "2") (pinfunction "2_2") (pintype "input"))
      (node (ref "C6") (pin "2") (pinfunction "2_2") (pintype "input"))
      (node (ref "C7") (pin "2") (pinfunction "2_2") (pintype "input"))
      (node (ref "CN1") (pin "3") (pinfunction "3_3") (pintype "unspecified"))
      (node (ref "CN2") (pin "2") (pinfunction "2_2") (pintype "unspecified"))
      (node (ref "CN3") (pin "2") (pinfunction "2_2") (pintype "unspecified"))
      (node (ref "CN4") (pin "2") (pinfunction "2_2") (pintype "unspecified"))
      (node (ref "CN5") (pin "2") (pinfunction "2_2") (pintype "unspecified"))
      (node (ref "CN6") (pin "2") (pinfunction "2_2") (pintype "unspecified"))
      (node (ref "CN7") (pin "2") (pinfunction "2_2") (pintype "unspecified"))
      (node (ref "CN8") (pin "2") (pinfunction "2_2") (pintype "unspecified"))
      (node (ref "D1") (pin "2") (pinfunction "A_2") (pintype "unspecified"))
      (node (ref "H1") (pin "3") (pinfunction "3_3") (pintype "unspecified"))
      (node (ref "H2") (pin "1") (pinfunction "1_1") (pintype "input"))
      (node (ref "H2") (pin "2") (pinfunction "2_2") (pintype "input"))
      (node (ref "H2") (pin "3") (pinfunction "3_3") (pintype "input"))
      (node (ref "H2") (pin "4") (pinfunction "4_4") (pintype "input"))
      (node (ref "H2") (pin "5") (pinfunction "5_5") (pintype "input"))
      (node (ref "H2") (pin "6") (pinfunction "6_6") (pintype "input"))
      (node (ref "LED4") (pin "1") (pinfunction "C_1") (pintype "input"))
      (node (ref "LED5") (pin "1") (pinfunction "C_1") (pintype "input"))
      (node (ref "LED6") (pin "1") (pinfunction "C_1") (pintype "input"))
      (node (ref "LED7") (pin "1") (pinfunction "C_1") (pintype "input"))
      (node (ref "P1") (pin "1") (pinfunction "1_1") (pintype "unspecified"))
      (node (ref "R4") (pin "1") (pinfunction "1_1") (pintype "input"))
      (node (ref "R7") (pin "2") (pinfunction "2_2") (pintype "input"))
      (node (ref "SW2") (pin "2") (pinfunction "2_2") (pintype "input"))
      (node (ref "U1") (pin "55") (pinfunction "55_55") (pintype "unspecified"))
      (node (ref "U1") (pin "56") (pinfunction "56_56") (pintype "unspecified"))
      (node (ref "U1") (pin "57") (pinfunction "57_57") (pintype "unspecified"))
      (node (ref "U1") (pin "58") (pinfunction "58_58") (pintype "unspecified"))
      (node (ref "U11") (pin "2") (pinfunction "GND_2") (pintype "unspecified"))
      (node (ref "U18") (pin "1") (pinfunction "GND_1") (pintype "unspecified"))
      (node (ref "U2") (pin "4") (pinfunction "GND_4") (pintype "unspecified"))
      (node (ref "U29") (pin "3") (pinfunction "GND_3") (pintype "unspecified"))
      (node (ref "USB1") (pin "5") (pinfunction "GND_5") (pintype "unspecified"))
    )
    (net (code "54") (name "HAND") (class "Default")
      (node (ref "CN1") (pin "2") (pinfunction "2_2") (pintype "unspecified"))
      (node (ref "U1") (pin "22") (pinfunction "22_22") (pintype "unspecified"))
    )
    (net (code "55") (name "IIC1_SCL") (class "Default")
      (node (ref "U14") (pin "23") (pinfunction "23_23") (pintype "unspecified"))
      (node (ref "U18") (pin "3") (pinfunction "SCL_3") (pintype "unspecified"))
    )
    (net (code "56") (name "IIC1_SDA") (class "Default")
      (node (ref "U14") (pin "22") (pinfunction "22_22") (pintype "unspecified"))
      (node (ref "U18") (pin "4") (pinfunction "SDA_4") (pintype "unspecified"))
    )
    (net (code "57") (name "JOINT1") (class "Default")
      (node (ref "U1") (pin "31") (pinfunction "31_31") (pintype "unspecified"))
      (node (ref "U16") (pin "1") (pinfunction "1_1") (pintype "unspecified"))
    )
    (net (code "58") (name "JOINT2") (class "Default")
      (node (ref "U1") (pin "20") (pinfunction "20_20") (pintype "unspecified"))
      (node (ref "U16") (pin "2") (pinfunction "2_2") (pintype "unspecified"))
    )
    (net (code "59") (name "JOINT3") (class "Default")
      (node (ref "U1") (pin "19") (pinfunction "19_19") (pintype "unspecified"))
      (node (ref "U16") (pin "3") (pinfunction "3_3") (pintype "unspecified"))
    )
    (net (code "60") (name "JOINT4") (class "Default")
      (node (ref "U1") (pin "53") (pinfunction "53_53") (pintype "unspecified"))
      (node (ref "U16") (pin "4") (pinfunction "4_4") (pintype "unspecified"))
    )
    (net (code "61") (name "JOINT5") (class "Default")
      (node (ref "U1") (pin "10") (pinfunction "10_10") (pintype "unspecified"))
      (node (ref "U16") (pin "5") (pinfunction "5_5") (pintype "unspecified"))
    )
    (net (code "62") (name "JOINT6") (class "Default")
      (node (ref "U1") (pin "17") (pinfunction "17_17") (pintype "unspecified"))
      (node (ref "U16") (pin "6") (pinfunction "6_6") (pintype "unspecified"))
    )
    (net (code "63") (name "K1") (class "Default")
      (node (ref "C51") (pin "1") (pinfunction "1_1") (pintype "input"))
      (node (ref "CN8") (pin "1") (pinfunction "1_1") (pintype "unspecified"))
      (node (ref "U14") (pin "16") (pinfunction "16_16") (pintype "unspecified"))
    )
    (net (code "64") (name "K2") (class "Default")
      (node (ref "C52") (pin "1") (pinfunction "1_1") (pintype "input"))
      (node (ref "CN2") (pin "1") (pinfunction "1_1") (pintype "unspecified"))
      (node (ref "U14") (pin "15") (pinfunction "15_15") (pintype "unspecified"))
    )
    (net (code "65") (name "K3") (class "Default")
      (node (ref "C53") (pin "1") (pinfunction "1_1") (pintype "input"))
      (node (ref "CN3") (pin "1") (pinfunction "1_1") (pintype "unspecified"))
      (node (ref "U14") (pin "28") (pinfunction "28_28") (pintype "unspecified"))
    )
    (net (code "66") (name "K4") (class "Default")
      (node (ref "C54") (pin "1") (pinfunction "1_1") (pintype "input"))
      (node (ref "CN4") (pin "1") (pinfunction "1_1") (pintype "unspecified"))
      (node (ref "U14") (pin "29") (pinfunction "29_29") (pintype "unspecified"))
    )
    (net (code "67") (name "K5") (class "Default")
      (node (ref "C55") (pin "1") (pinfunction "1_1") (pintype "input"))
      (node (ref "CN5") (pin "1") (pinfunction "1_1") (pintype "unspecified"))
      (node (ref "U14") (pin "30") (pinfunction "30_30") (pintype "unspecified"))
    )
    (net (code "68") (name "K6") (class "Default")
      (node (ref "C56") (pin "1") (pinfunction "1_1") (pintype "input"))
      (node (ref "CN6") (pin "1") (pinfunction "1_1") (pintype "unspecified"))
      (node (ref "U14") (pin "31") (pinfunction "31_31") (pintype "unspecified"))
    )
    (net (code "69") (name "KEY1") (class "Default")
      (node (ref "C58") (pin "1") (pinfunction "1_1") (pintype "input"))
      (node (ref "SW2") (pin "1") (pinfunction "1_1") (pintype "input"))
      (node (ref "U14") (pin "17") (pinfunction "17_17") (pintype "unspecified"))
    )
    (net (code "70") (name "K_HAND") (class "Default")
      (node (ref "C57") (pin "1") (pinfunction "1_1") (pintype "input"))
      (node (ref "CN7") (pin "1") (pinfunction "1_1") (pintype "unspecified"))
      (node (ref "U14") (pin "34") (pinfunction "34_34") (pintype "unspecified"))
    )
    (net (code "71") (name "LED1") (class "Default")
      (node (ref "LED6") (pin "2") (pinfunction "A_2") (pintype "input"))
      (node (ref "U14") (pin "20") (pinfunction "20_20") (pintype "unspecified"))
    )
    (net (code "72") (name "LED2") (class "Default")
      (node (ref "LED5") (pin "2") (pinfunction "A_2") (pintype "input"))
      (node (ref "U14") (pin "18") (pinfunction "18_18") (pintype "unspecified"))
    )
    (net (code "73") (name "Net-(C8-Pad1)") (class "Default")
      (node (ref "C8") (pin "1") (pinfunction "1_1") (pintype "input"))
      (node (ref "R2") (pin "2") (pinfunction "2_2") (pintype "input"))
    )
    (net (code "74") (name "Net-(C9-Pad1)") (class "Default")
      (node (ref "C9") (pin "1") (pinfunction "1_1") (pintype "input"))
      (node (ref "R3") (pin "2") (pinfunction "2_2") (pintype "input"))
      (node (ref "R4") (pin "2") (pinfunction "2_2") (pintype "input"))
      (node (ref "R5") (pin "1") (pinfunction "1_1") (pintype "input"))
    )
    (net (code "75") (name "Net-(LED4-A)") (class "Default")
      (node (ref "LED4") (pin "2") (pinfunction "A_2") (pintype "input"))
      (node (ref "R24") (pin "1") (pinfunction "1_1") (pintype "input"))
    )
    (net (code "76") (name "Net-(LED7-A)") (class "Default")
      (node (ref "LED7") (pin "2") (pinfunction "A_2") (pintype "input"))
      (node (ref "R9") (pin "1") (pinfunction "1_1") (pintype "input"))
    )
    (net (code "77") (name "Net-(U2-AAM)") (class "Default")
      (node (ref "R6") (pin "1") (pinfunction "1_1") (pintype "input"))
      (node (ref "R7") (pin "1") (pinfunction "1_1") (pintype "input"))
      (node (ref "U2") (pin "1") (pinfunction "AAM_1") (pintype "unspecified"))
    )
    (net (code "78") (name "Net-(U2-BST)") (class "Default")
      (node (ref "R2") (pin "1") (pinfunction "1_1") (pintype "input"))
      (node (ref "U2") (pin "5") (pinfunction "BST_5") (pintype "unspecified"))
    )
    (net (code "79") (name "Net-(U2-EN)") (class "Default")
      (node (ref "R1") (pin "2") (pinfunction "2_2") (pintype "input"))
      (node (ref "U2") (pin "6") (pinfunction "EN_6") (pintype "unspecified"))
    )
    (net (code "80") (name "Net-(U2-FB)") (class "Default")
      (node (ref "R5") (pin "2") (pinfunction "2_2") (pintype "input"))
      (node (ref "U2") (pin "8") (pinfunction "FB_8") (pintype "unspecified"))
    )
    (net (code "81") (name "Net-(U2-SW)") (class "Default")
      (node (ref "C8") (pin "2") (pinfunction "2_2") (pintype "input"))
      (node (ref "L2") (pin "1") (pinfunction "1_1") (pintype "unspecified"))
      (node (ref "U2") (pin "3") (pinfunction "SW_3") (pintype "unspecified"))
    )
    (net (code "82") (name "Net-(U2-VCC)") (class "Default")
      (node (ref "C4") (pin "2") (pinfunction "2_2") (pintype "input"))
      (node (ref "R6") (pin "2") (pinfunction "2_2") (pintype "input"))
      (node (ref "U2") (pin "7") (pinfunction "VCC_7") (pintype "unspecified"))
    )
    (net (code "83") (name "Net-(U29-V3)") (class "Default")
      (node (ref "C50") (pin "1") (pinfunction "1_1") (pintype "input"))
      (node (ref "U29") (pin "8") (pinfunction "V3_8") (pintype "unspecified"))
    )
    (net (code "84") (name "USB2_D+") (class "Default")
      (node (ref "U29") (pin "1") (pinfunction "UD+_1") (pintype "unspecified"))
      (node (ref "USB1") (pin "3") (pinfunction "D+_3") (pintype "unspecified"))
    )
    (net (code "85") (name "USB2_D-") (class "Default")
      (node (ref "U29") (pin "2") (pinfunction "UD-_2") (pintype "unspecified"))
      (node (ref "USB1") (pin "2") (pinfunction "D-_2") (pintype "unspecified"))
    )
    (net (code "86") (name "unconnected-(H14-Pad1)") (class "Default")
      (node (ref "H14") (pin "1") (pinfunction "1_1") (pintype "unspecified+no_connect"))
    )
    (net (code "87") (name "unconnected-(H14-Pad2)") (class "Default")
      (node (ref "H14") (pin "2") (pinfunction "2_2") (pintype "unspecified+no_connect"))
    )
    (net (code "88") (name "unconnected-(H14-Pad3)") (class "Default")
      (node (ref "H14") (pin "3") (pinfunction "3_3") (pintype "unspecified+no_connect"))
    )
    (net (code "89") (name "unconnected-(H14-Pad4)") (class "Default")
      (node (ref "H14") (pin "4") (pinfunction "4_4") (pintype "unspecified+no_connect"))
    )
    (net (code "90") (name "unconnected-(H14-Pad5)") (class "Default")
      (node (ref "H14") (pin "5") (pinfunction "5_5") (pintype "unspecified+no_connect"))
    )
    (net (code "91") (name "unconnected-(H14-Pad6)") (class "Default")
      (node (ref "H14") (pin "6") (pinfunction "6_6") (pintype "unspecified+no_connect"))
    )
    (net (code "92") (name "unconnected-(H14-Pad7)") (class "Default")
      (node (ref "H14") (pin "7") (pinfunction "7_7") (pintype "unspecified+no_connect"))
    )
    (net (code "93") (name "unconnected-(H14-Pad8)") (class "Default")
      (node (ref "H14") (pin "8") (pinfunction "8_8") (pintype "unspecified+no_connect"))
    )
    (net (code "94") (name "unconnected-(H14-Pad9)") (class "Default")
      (node (ref "H14") (pin "9") (pinfunction "9_9") (pintype "unspecified+no_connect"))
    )
    (net (code "95") (name "unconnected-(H14-Pad10)") (class "Default")
      (node (ref "H14") (pin "10") (pinfunction "10_10") (pintype "unspecified+no_connect"))
    )
    (net (code "96") (name "unconnected-(SCREW1-Pad1)") (class "Default")
      (node (ref "SCREW1") (pin "1") (pinfunction "1_1") (pintype "input+no_connect"))
    )
    (net (code "97") (name "unconnected-(SCREW2-Pad1)") (class "Default")
      (node (ref "SCREW2") (pin "1") (pinfunction "1_1") (pintype "input+no_connect"))
    )
    (net (code "98") (name "unconnected-(SCREW3-Pad1)") (class "Default")
      (node (ref "SCREW3") (pin "1") (pinfunction "1_1") (pintype "input+no_connect"))
    )
    (net (code "99") (name "unconnected-(SCREW4-Pad1)") (class "Default")
      (node (ref "SCREW4") (pin "1") (pinfunction "1_1") (pintype "input+no_connect"))
    )
    (net (code "100") (name "unconnected-(U1-Pad5)") (class "Default")
      (node (ref "U1") (pin "5") (pinfunction "5_5") (pintype "unspecified+no_connect"))
    )
    (net (code "101") (name "unconnected-(U1-Pad6)") (class "Default")
      (node (ref "U1") (pin "6") (pinfunction "6_6") (pintype "unspecified+no_connect"))
    )
    (net (code "102") (name "unconnected-(U1-Pad7)") (class "Default")
      (node (ref "U1") (pin "7") (pinfunction "7_7") (pintype "unspecified+no_connect"))
    )
    (net (code "103") (name "unconnected-(U1-Pad8)") (class "Default")
      (node (ref "U1") (pin "8") (pinfunction "8_8") (pintype "unspecified+no_connect"))
    )
    (net (code "104") (name "unconnected-(U1-Pad11)") (class "Default")
      (node (ref "U1") (pin "11") (pinfunction "11_11") (pintype "unspecified+no_connect"))
    )
    (net (code "105") (name "unconnected-(U1-Pad14)") (class "Default")
      (node (ref "U1") (pin "14") (pinfunction "14_14") (pintype "unspecified+no_connect"))
    )
    (net (code "106") (name "unconnected-(U1-Pad23)") (class "Default")
      (node (ref "U1") (pin "23") (pinfunction "23_23") (pintype "unspecified+no_connect"))
    )
    (net (code "107") (name "unconnected-(U1-Pad25)") (class "Default")
      (node (ref "U1") (pin "25") (pinfunction "25_25") (pintype "unspecified+no_connect"))
    )
    (net (code "108") (name "unconnected-(U1-Pad26)") (class "Default")
      (node (ref "U1") (pin "26") (pinfunction "26_26") (pintype "unspecified+no_connect"))
    )
    (net (code "109") (name "unconnected-(U1-Pad27)") (class "Default")
      (node (ref "U1") (pin "27") (pinfunction "27_27") (pintype "unspecified+no_connect"))
    )
    (net (code "110") (name "unconnected-(U1-Pad28)") (class "Default")
      (node (ref "U1") (pin "28") (pinfunction "28_28") (pintype "unspecified+no_connect"))
    )
    (net (code "111") (name "unconnected-(U1-Pad29)") (class "Default")
      (node (ref "U1") (pin "29") (pinfunction "29_29") (pintype "unspecified+no_connect"))
    )
    (net (code "112") (name "unconnected-(U1-Pad30)") (class "Default")
      (node (ref "U1") (pin "30") (pinfunction "30_30") (pintype "unspecified+no_connect"))
    )
    (net (code "113") (name "unconnected-(U1-Pad32)") (class "Default")
      (node (ref "U1") (pin "32") (pinfunction "32_32") (pintype "unspecified+no_connect"))
    )
    (net (code "114") (name "unconnected-(U1-Pad33)") (class "Default")
      (node (ref "U1") (pin "33") (pinfunction "33_33") (pintype "unspecified+no_connect"))
    )
    (net (code "115") (name "unconnected-(U1-Pad34)") (class "Default")
      (node (ref "U1") (pin "34") (pinfunction "34_34") (pintype "unspecified+no_connect"))
    )
    (net (code "116") (name "unconnected-(U1-Pad35)") (class "Default")
      (node (ref "U1") (pin "35") (pinfunction "35_35") (pintype "unspecified+no_connect"))
    )
    (net (code "117") (name "unconnected-(U1-Pad36)") (class "Default")
      (node (ref "U1") (pin "36") (pinfunction "36_36") (pintype "unspecified+no_connect"))
    )
    (net (code "118") (name "unconnected-(U1-Pad37)") (class "Default")
      (node (ref "U1") (pin "37") (pinfunction "37_37") (pintype "unspecified+no_connect"))
    )
    (net (code "119") (name "unconnected-(U1-Pad40)") (class "Default")
      (node (ref "U1") (pin "40") (pinfunction "40_40") (pintype "unspecified+no_connect"))
    )
    (net (code "120") (name "unconnected-(U1-Pad41)") (class "Default")
      (node (ref "U1") (pin "41") (pinfunction "41_41") (pintype "unspecified+no_connect"))
    )
    (net (code "121") (name "unconnected-(U1-Pad42)") (class "Default")
      (node (ref "U1") (pin "42") (pinfunction "42_42") (pintype "unspecified+no_connect"))
    )
    (net (code "122") (name "unconnected-(U1-Pad43)") (class "Default")
      (node (ref "U1") (pin "43") (pinfunction "43_43") (pintype "unspecified+no_connect"))
    )
    (net (code "123") (name "unconnected-(U11-NC-Pad4)") (class "Default")
      (node (ref "U11") (pin "4") (pinfunction "NC_4") (pintype "unspecified+no_connect"))
    )
    (net (code "124") (name "unconnected-(U14-Pad1)") (class "Default")
      (node (ref "U14") (pin "1") (pinfunction "1_1") (pintype "unspecified+no_connect"))
    )
    (net (code "125") (name "unconnected-(U14-Pad2)") (class "Default")
      (node (ref "U14") (pin "2") (pinfunction "2_2") (pintype "unspecified+no_connect"))
    )
    (net (code "126") (name "unconnected-(U14-Pad3)") (class "Default")
      (node (ref "U14") (pin "3") (pinfunction "3_3") (pintype "unspecified+no_connect"))
    )
    (net (code "127") (name "unconnected-(U14-Pad4)") (class "Default")
      (node (ref "U14") (pin "4") (pinfunction "4_4") (pintype "unspecified+no_connect"))
    )
    (net (code "128") (name "unconnected-(U14-Pad5)") (class "Default")
      (node (ref "U14") (pin "5") (pinfunction "5_5") (pintype "unspecified+no_connect"))
    )
    (net (code "129") (name "unconnected-(U14-Pad6)") (class "Default")
      (node (ref "U14") (pin "6") (pinfunction "6_6") (pintype "unspecified+no_connect"))
    )
    (net (code "130") (name "unconnected-(U14-Pad7)") (class "Default")
      (node (ref "U14") (pin "7") (pinfunction "7_7") (pintype "unspecified+no_connect"))
    )
    (net (code "131") (name "unconnected-(U14-Pad10)") (class "Default")
      (node (ref "U14") (pin "10") (pinfunction "10_10") (pintype "unspecified+no_connect"))
    )
    (net (code "132") (name "unconnected-(U14-Pad11)") (class "Default")
      (node (ref "U14") (pin "11") (pinfunction "11_11") (pintype "unspecified+no_connect"))
    )
    (net (code "133") (name "unconnected-(U14-Pad12)") (class "Default")
      (node (ref "U14") (pin "12") (pinfunction "12_12") (pintype "unspecified+no_connect"))
    )
    (net (code "134") (name "unconnected-(U14-Pad13)") (class "Default")
      (node (ref "U14") (pin "13") (pinfunction "13_13") (pintype "unspecified+no_connect"))
    )
    (net (code "135") (name "unconnected-(U14-Pad14)") (class "Default")
      (node (ref "U14") (pin "14") (pinfunction "14_14") (pintype "unspecified+no_connect"))
    )
    (net (code "136") (name "unconnected-(U14-Pad19)") (class "Default")
      (node (ref "U14") (pin "19") (pinfunction "19_19") (pintype "unspecified+no_connect"))
    )
    (net (code "137") (name "unconnected-(U14-Pad27)") (class "Default")
      (node (ref "U14") (pin "27") (pinfunction "27_27") (pintype "unspecified+no_connect"))
    )
    (net (code "138") (name "unconnected-(U14-Pad49)") (class "Default")
      (node (ref "U14") (pin "49") (pinfunction "49_49") (pintype "unspecified+no_connect"))
    )
    (net (code "139") (name "unconnected-(U14-Pad50)") (class "Default")
      (node (ref "U14") (pin "50") (pinfunction "50_50") (pintype "unspecified+no_connect"))
    )
    (net (code "140") (name "unconnected-(U14-Pad51)") (class "Default")
      (node (ref "U14") (pin "51") (pinfunction "51_51") (pintype "unspecified+no_connect"))
    )
    (net (code "141") (name "unconnected-(U14-Pad52)") (class "Default")
      (node (ref "U14") (pin "52") (pinfunction "52_52") (pintype "unspecified+no_connect"))
    )
    (net (code "142") (name "unconnected-(U29-RTS#-Pad4)") (class "Default")
      (node (ref "U29") (pin "4") (pinfunction "RTS#_4") (pintype "unspecified+no_connect"))
    )
    (net (code "143") (name "unconnected-(USB1-ID-Pad4)") (class "Default")
      (node (ref "USB1") (pin "4") (pinfunction "ID_4") (pintype "unspecified+no_connect"))
    )
    (net (code "144") (name "unconnected-(USB1-SH1-Pad6)") (class "Default")
      (node (ref "USB1") (pin "6") (pinfunction "SH1_6") (pintype "unspecified+no_connect"))
    )
    (net (code "145") (name "unconnected-(USB1-SH2-Pad7)") (class "Default")
      (node (ref "USB1") (pin "7") (pinfunction "SH2_7") (pintype "unspecified+no_connect"))
    )
    (net (code "146") (name "unconnected-(USB1-SH3-Pad8)") (class "Default")
      (node (ref "USB1") (pin "8") (pinfunction "SH3_8") (pintype "unspecified+no_connect"))
    )
    (net (code "147") (name "unconnected-(USB1-SH4-Pad9)") (class "Default")
      (node (ref "USB1") (pin "9") (pinfunction "SH4_9") (pintype "unspecified+no_connect"))
    )
  )
)
